# HumiditySensor.net
KiCad netlist of a schematic drawn in Altium Designer
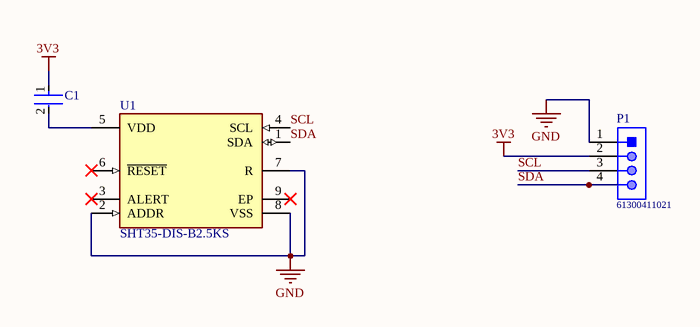
[diagram p0: HumiditySensor.SchDoc]

(export (version "E")
  (design (tool "Eeschema 10.0.6"))
  (components
    (comp (ref "C1")
      (value "CGA2B1X7R1C104K050BC")
      (footprint "FP-CGA2B-IPC_C")
      (description "Cap Ceramic 100nF 16V X7R 10% Pad SMD 0402 +125°C Automotive T/R")
      (fields (field (name "TOLERANCE") "10%"))
      (libsource (lib "Altium Content Vault") (part "b4654b650e69147ec39a6b967a45e02"))
    )
    (comp (ref "P1")
      (value "61300411021")
      (footprint "61300411021")
      (description "THT Angled Pin Header WR-PHD, Pitch 2.54 mm, Single Row, 4 pins")
      (fields (field (name "MANUFACTURER") "Wurth Elektronik") (field (name "PUBLISHER") "WurthElektronik"))
      (libsource (lib "Altium Content Vault") (part "WE-CN-1P-M-R4"))
    )
    (comp (ref "U1")
      (value "SHT35-DIS-B2.5KS")
      (footprint "FP-SHT35-DIS-B2_5KS-MFG")
      (description "SENSOR HUMI/TEMP 5V I2C 1.5% SMD")
      (libsource (lib "Altium Content Vault") (part "8f0571ed437043a03774594e9828022"))
    )
  )
  (nets
    (net (code "1") (name "/SCL") (class "Default")
      (node (ref "P1") (pin "3") (pinfunction "3_3") (pintype "passive"))
      (node (ref "U1") (pin "4") (pinfunction "SCL_4") (pintype "input"))
    )
    (net (code "2") (name "/SDA") (class "Default")
      (node (ref "P1") (pin "4") (pinfunction "4_4") (pintype "passive"))
      (node (ref "U1") (pin "1") (pinfunction "SDA_1") (pintype "bidirectional"))
    )
    (net (code "3") (name "3V3") (class "Default")
      (node (ref "C1") (pin "1") (pinfunction "1_1") (pintype "passive"))
      (node (ref "P1") (pin "2") (pinfunction "2_2") (pintype "passive"))
    )
    (net (code "4") (name "GND") (class "Default")
      (node (ref "P1") (pin "1") (pinfunction "1_1") (pintype "passive"))
      (node (ref "U1") (pin "2") (pinfunction "ADDR_2") (pintype "input"))
      (node (ref "U1") (pin "7") (pinfunction "R_7") (pintype "passive"))
      (node (ref "U1") (pin "8") (pinfunction "VSS_8") (pintype "power_in"))
    )
    (net (code "5") (name "Net-(U1-VDD)") (class "Default")
      (node (ref "C1") (pin "2") (pinfunction "2_2") (pintype "passive"))
      (node (ref "U1") (pin "5") (pinfunction "VDD_5") (pintype "power_in"))
    )
    (net (code "6") (name "unconnected-(U1-ALERT-Pad3)") (class "Default")
      (node (ref "U1") (pin "3") (pinfunction "ALERT_3") (pintype "open_collector+no_connect"))
    )
    (net (code "7") (name "unconnected-(U1-EP-Pad9)") (class "Default")
      (node (ref "U1") (pin "9") (pinfunction "EP_9") (pintype "passive+no_connect"))
    )
    (net (code "8") (name "unconnected-(U1-~{RESET}-Pad6)") (class "Default")
      (node (ref "U1") (pin "6") (pinfunction "~{RESET}_6") (pintype "input+no_connect"))
    )
  )
)
